# maXTouch_Xplained_Shield.net
KiCad netlist of a schematic drawn in EAGLE
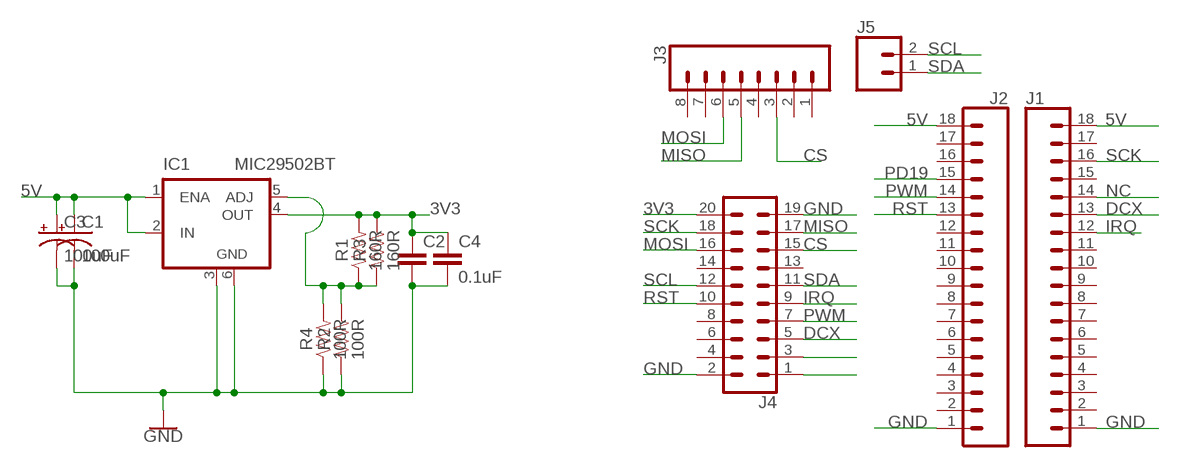
[diagram p0: schematic, sheet 1]

(export (version "E")
  (design (tool "Eeschema 10.0.6"))
  (components
    (comp (ref "C1")
      (value "100uF")
      (footprint "eagle-import:PANASONIC_D")
      (libsource (lib "eagle-import") (part "100UF-POLAR-25V-20%(ELEC)"))
    )
    (comp (ref "C2")
      (value "10uF")
      (footprint "eagle-import:1206")
      (libsource (lib "eagle-import") (part "CAP-1206"))
    )
    (comp (ref "C3")
      (value "100uF")
      (footprint "eagle-import:CPOL-RADIAL-2.5MM-6.5MM")
      (libsource (lib "eagle-import") (part "100UF-POLAR-RADIAL-2.5MM-25V-20%"))
    )
    (comp (ref "C4")
      (value "0.1uF")
      (footprint "eagle-import:CAP-PTH-SMALL-KIT")
      (libsource (lib "eagle-import") (part "0.1UF-KIT-EZ-50V-20%"))
    )
    (comp (ref "IC1")
      (value "MIC29502BT")
      (footprint "eagle-import:TO263-5")
      (libsource (lib "eagle-import") (part "MIC29502BT"))
    )
    (comp (ref "J1")
      (value "CONN_18SILK")
      (footprint "eagle-import:1X18")
      (libsource (lib "eagle-import") (part "CONN_18SILK"))
    )
    (comp (ref "J2")
      (value "CONN_18SILK")
      (footprint "eagle-import:1X18")
      (libsource (lib "eagle-import") (part "CONN_18SILK"))
    )
    (comp (ref "J3")
      (value "CONN_08\"")
      (footprint "eagle-import:1X08")
      (libsource (lib "eagle-import") (part "CONN_08{dblquote}"))
    )
    (comp (ref "J4")
      (value "CONN_10X2")
      (footprint "eagle-import:2X10")
      (libsource (lib "eagle-import") (part "CONN_10X2"))
    )
    (comp (ref "J5")
      (value "CONN_02")
      (footprint "eagle-import:1X02")
      (libsource (lib "eagle-import") (part "CONN_02"))
    )
    (comp (ref "R1")
      (value "160R")
      (footprint "eagle-import:1206")
      (libsource (lib "eagle-import") (part "RESISTOR1206"))
    )
    (comp (ref "R2")
      (value "100R")
      (footprint "eagle-import:1206")
      (libsource (lib "eagle-import") (part "RESISTOR1206"))
    )
    (comp (ref "R3")
      (value "160R")
      (footprint "eagle-import:AXIAL-0.3-KIT")
      (libsource (lib "eagle-import") (part "RESISTORAXIAL-0.3-KIT"))
    )
    (comp (ref "R4")
      (value "100R")
      (footprint "eagle-import:AXIAL-0.3-KIT")
      (libsource (lib "eagle-import") (part "RESISTORAXIAL-0.3-KIT"))
    )
  )
  (nets
    (net (code "1") (name "/3V3") (class "Default")
      (node (ref "C2") (pin "1") (pinfunction "1_1") (pintype "passive"))
      (node (ref "C4") (pin "1") (pinfunction "1_1") (pintype "passive"))
      (node (ref "IC1") (pin "4") (pinfunction "OUT_4") (pintype "passive"))
      (node (ref "J4") (pin "20") (pinfunction "20_20") (pintype "passive"))
      (node (ref "R1") (pin "2") (pinfunction "2_2") (pintype "passive"))
      (node (ref "R3") (pin "P$2") (pinfunction "2_P$2") (pintype "passive"))
    )
    (net (code "2") (name "/5V") (class "Default")
      (node (ref "C1") (pin "+") (pinfunction "+_+") (pintype "passive"))
      (node (ref "C3") (pin "1") (pinfunction "+_1") (pintype "passive"))
      (node (ref "IC1") (pin "1") (pinfunction "ENA_1") (pintype "input"))
      (node (ref "IC1") (pin "2") (pinfunction "IN_2") (pintype "passive"))
      (node (ref "J1") (pin "18") (pinfunction "18_18") (pintype "passive"))
      (node (ref "J2") (pin "18") (pinfunction "18_18") (pintype "passive"))
    )
    (net (code "3") (name "/CS") (class "Default")
      (node (ref "J3") (pin "3") (pinfunction "3_3") (pintype "passive"))
      (node (ref "J4") (pin "15") (pinfunction "15_15") (pintype "passive"))
    )
    (net (code "4") (name "/DCX") (class "Default")
      (node (ref "J1") (pin "13") (pinfunction "13_13") (pintype "passive"))
      (node (ref "J4") (pin "5") (pinfunction "5_5") (pintype "passive"))
    )
    (net (code "5") (name "/IRQ") (class "Default")
      (node (ref "J1") (pin "12") (pinfunction "12_12") (pintype "passive"))
      (node (ref "J4") (pin "9") (pinfunction "9_9") (pintype "passive"))
    )
    (net (code "6") (name "/MISO") (class "Default")
      (node (ref "J3") (pin "5") (pinfunction "5_5") (pintype "passive"))
      (node (ref "J4") (pin "17") (pinfunction "17_17") (pintype "passive"))
    )
    (net (code "7") (name "/MOSI") (class "Default")
      (node (ref "J3") (pin "6") (pinfunction "6_6") (pintype "passive"))
      (node (ref "J4") (pin "16") (pinfunction "16_16") (pintype "passive"))
    )
    (net (code "8") (name "/NC") (class "Default")
      (node (ref "J1") (pin "14") (pinfunction "14_14") (pintype "passive"))
    )
    (net (code "9") (name "/PD19") (class "Default")
      (node (ref "J2") (pin "15") (pinfunction "15_15") (pintype "passive"))
    )
    (net (code "10") (name "/PWM") (class "Default")
      (node (ref "J2") (pin "14") (pinfunction "14_14") (pintype "passive"))
      (node (ref "J4") (pin "7") (pinfunction "7_7") (pintype "passive"))
    )
    (net (code "11") (name "/RST") (class "Default")
      (node (ref "J2") (pin "13") (pinfunction "13_13") (pintype "passive"))
      (node (ref "J4") (pin "10") (pinfunction "10_10") (pintype "passive"))
    )
    (net (code "12") (name "/SCK") (class "Default")
      (node (ref "J1") (pin "16") (pinfunction "16_16") (pintype "passive"))
      (node (ref "J4") (pin "18") (pinfunction "18_18") (pintype "passive"))
    )
    (net (code "13") (name "/SCL") (class "Default")
      (node (ref "J4") (pin "12") (pinfunction "12_12") (pintype "passive"))
      (node (ref "J5") (pin "2") (pinfunction "2_2") (pintype "passive"))
    )
    (net (code "14") (name "/SDA") (class "Default")
      (node (ref "J4") (pin "11") (pinfunction "11_11") (pintype "passive"))
      (node (ref "J5") (pin "1") (pinfunction "1_1") (pintype "passive"))
    )
    (net (code "15") (name "GND") (class "Default")
      (node (ref "C1") (pin "-") (pinfunction "-_-") (pintype "passive"))
      (node (ref "C2") (pin "2") (pinfunction "2_2") (pintype "passive"))
      (node (ref "C3") (pin "2") (pinfunction "-_2") (pintype "passive"))
      (node (ref "C4") (pin "2") (pinfunction "2_2") (pintype "passive"))
      (node (ref "IC1") (pin "3") (pinfunction "GND_3") (pintype "power_in"))
      (node (ref "IC1") (pin "6") (pinfunction "GND_6") (pintype "power_in"))
      (node (ref "J1") (pin "1") (pinfunction "1_1") (pintype "passive"))
      (node (ref "J2") (pin "1") (pinfunction "1_1") (pintype "passive"))
      (node (ref "J4") (pin "19") (pinfunction "19_19") (pintype "passive"))
      (node (ref "J4") (pin "2") (pinfunction "2_2") (pintype "passive"))
      (node (ref "R2") (pin "1") (pinfunction "1_1") (pintype "passive"))
      (node (ref "R4") (pin "P$1") (pinfunction "1_P$1") (pintype "passive"))
    )
    (net (code "16") (name "Net-(IC1-ADJ)") (class "Default")
      (node (ref "IC1") (pin "5") (pinfunction "ADJ_5") (pintype "input"))
      (node (ref "R1") (pin "1") (pinfunction "1_1") (pintype "passive"))
      (node (ref "R2") (pin "2") (pinfunction "2_2") (pintype "passive"))
      (node (ref "R3") (pin "P$1") (pinfunction "1_P$1") (pintype "passive"))
      (node (ref "R4") (pin "P$2") (pinfunction "2_P$2") (pintype "passive"))
    )
    (net (code "17") (name "unconnected-(J1-Pad2)") (class "Default")
      (node (ref "J1") (pin "2") (pinfunction "2_2") (pintype "passive"))
    )
    (net (code "18") (name "unconnected-(J1-Pad3)") (class "Default")
      (node (ref "J1") (pin "3") (pinfunction "3_3") (pintype "passive"))
    )
    (net (code "19") (name "unconnected-(J1-Pad4)") (class "Default")
      (node (ref "J1") (pin "4") (pinfunction "4_4") (pintype "passive"))
    )
    (net (code "20") (name "unconnected-(J1-Pad5)") (class "Default")
      (node (ref "J1") (pin "5") (pinfunction "5_5") (pintype "passive"))
    )
    (net (code "21") (name "unconnected-(J1-Pad6)") (class "Default")
      (node (ref "J1") (pin "6") (pinfunction "6_6") (pintype "passive"))
    )
    (net (code "22") (name "unconnected-(J1-Pad7)") (class "Default")
      (node (ref "J1") (pin "7") (pinfunction "7_7") (pintype "passive"))
    )
    (net (code "23") (name "unconnected-(J1-Pad8)") (class "Default")
      (node (ref "J1") (pin "8") (pinfunction "8_8") (pintype "passive"))
    )
    (net (code "24") (name "unconnected-(J1-Pad9)") (class "Default")
      (node (ref "J1") (pin "9") (pinfunction "9_9") (pintype "passive"))
    )
    (net (code "25") (name "unconnected-(J1-Pad10)") (class "Default")
      (node (ref "J1") (pin "10") (pinfunction "10_10") (pintype "passive"))
    )
    (net (code "26") (name "unconnected-(J1-Pad11)") (class "Default")
      (node (ref "J1") (pin "11") (pinfunction "11_11") (pintype "passive"))
    )
    (net (code "27") (name "unconnected-(J1-Pad15)") (class "Default")
      (node (ref "J1") (pin "15") (pinfunction "15_15") (pintype "passive"))
    )
    (net (code "28") (name "unconnected-(J1-Pad17)") (class "Default")
      (node (ref "J1") (pin "17") (pinfunction "17_17") (pintype "passive"))
    )
    (net (code "29") (name "unconnected-(J2-Pad2)") (class "Default")
      (node (ref "J2") (pin "2") (pinfunction "2_2") (pintype "passive"))
    )
    (net (code "30") (name "unconnected-(J2-Pad3)") (class "Default")
      (node (ref "J2") (pin "3") (pinfunction "3_3") (pintype "passive"))
    )
    (net (code "31") (name "unconnected-(J2-Pad4)") (class "Default")
      (node (ref "J2") (pin "4") (pinfunction "4_4") (pintype "passive"))
    )
    (net (code "32") (name "unconnected-(J2-Pad5)") (class "Default")
      (node (ref "J2") (pin "5") (pinfunction "5_5") (pintype "passive"))
    )
    (net (code "33") (name "unconnected-(J2-Pad6)") (class "Default")
      (node (ref "J2") (pin "6") (pinfunction "6_6") (pintype "passive"))
    )
    (net (code "34") (name "unconnected-(J2-Pad7)") (class "Default")
      (node (ref "J2") (pin "7") (pinfunction "7_7") (pintype "passive"))
    )
    (net (code "35") (name "unconnected-(J2-Pad8)") (class "Default")
      (node (ref "J2") (pin "8") (pinfunction "8_8") (pintype "passive"))
    )
    (net (code "36") (name "unconnected-(J2-Pad9)") (class "Default")
      (node (ref "J2") (pin "9") (pinfunction "9_9") (pintype "passive"))
    )
    (net (code "37") (name "unconnected-(J2-Pad10)") (class "Default")
      (node (ref "J2") (pin "10") (pinfunction "10_10") (pintype "passive"))
    )
    (net (code "38") (name "unconnected-(J2-Pad11)") (class "Default")
      (node (ref "J2") (pin "11") (pinfunction "11_11") (pintype "passive"))
    )
    (net (code "39") (name "unconnected-(J2-Pad12)") (class "Default")
      (node (ref "J2") (pin "12") (pinfunction "12_12") (pintype "passive"))
    )
    (net (code "40") (name "unconnected-(J2-Pad16)") (class "Default")
      (node (ref "J2") (pin "16") (pinfunction "16_16") (pintype "passive"))
    )
    (net (code "41") (name "unconnected-(J2-Pad17)") (class "Default")
      (node (ref "J2") (pin "17") (pinfunction "17_17") (pintype "passive"))
    )
    (net (code "42") (name "unconnected-(J3-Pad1)") (class "Default")
      (node (ref "J3") (pin "1") (pinfunction "1_1") (pintype "passive"))
    )
    (net (code "43") (name "unconnected-(J3-Pad2)") (class "Default")
      (node (ref "J3") (pin "2") (pinfunction "2_2") (pintype "passive"))
    )
    (net (code "44") (name "unconnected-(J3-Pad4)") (class "Default")
      (node (ref "J3") (pin "4") (pinfunction "4_4") (pintype "passive"))
    )
    (net (code "45") (name "unconnected-(J3-Pad7)") (class "Default")
      (node (ref "J3") (pin "7") (pinfunction "7_7") (pintype "passive"))
    )
    (net (code "46") (name "unconnected-(J3-Pad8)") (class "Default")
      (node (ref "J3") (pin "8") (pinfunction "8_8") (pintype "passive"))
    )
    (net (code "47") (name "unconnected-(J4-Pad1)") (class "Default")
      (node (ref "J4") (pin "1") (pinfunction "1_1") (pintype "passive"))
    )
    (net (code "48") (name "unconnected-(J4-Pad3)") (class "Default")
      (node (ref "J4") (pin "3") (pinfunction "3_3") (pintype "passive"))
    )
    (net (code "49") (name "unconnected-(J4-Pad4)") (class "Default")
      (node (ref "J4") (pin "4") (pinfunction "4_4") (pintype "passive"))
    )
    (net (code "50") (name "unconnected-(J4-Pad6)") (class "Default")
      (node (ref "J4") (pin "6") (pinfunction "6_6") (pintype "passive"))
    )
    (net (code "51") (name "unconnected-(J4-Pad8)") (class "Default")
      (node (ref "J4") (pin "8") (pinfunction "8_8") (pintype "passive"))
    )
    (net (code "52") (name "unconnected-(J4-Pad13)") (class "Default")
      (node (ref "J4") (pin "13") (pinfunction "13_13") (pintype "passive"))
    )
    (net (code "53") (name "unconnected-(J4-Pad14)") (class "Default")
      (node (ref "J4") (pin "14") (pinfunction "14_14") (pintype "passive"))
    )
  )
)
